# FMC_EEPROM.net
KiCad netlist of a schematic drawn in Altium Designer
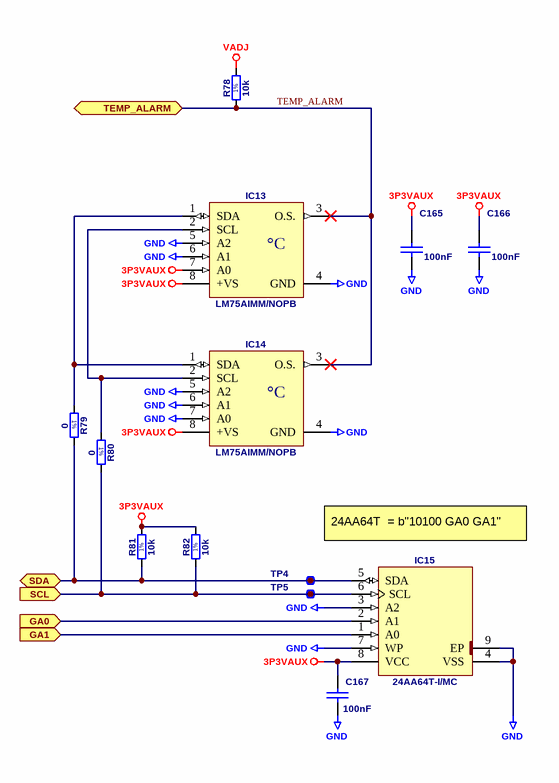
[diagram p0: FMC_EEPROM.SchDoc]

(export (version "E")
  (design (tool "Eeschema 10.0.6"))
  (components
    (comp (ref "C165")
      (value "100nF")
      (footprint "CAPC0603X33N")
      (description "Non-polarised capacitor")
      (fields
        (field (name "PART NUMBER") "CC0201_100NF_6.3V_10%_X5R")
        (field (name "VOLTAGE") "6.3V")
        (field (name "AUTHOR") "CERN DEM JLC")
      )
      (libsource (lib "Capacitors") (part "Capacitor - non polarized"))
    )
    (comp (ref "C166")
      (value "100nF")
      (footprint "CAPC0603X33N")
      (description "Non-polarised capacitor")
      (fields
        (field (name "PART NUMBER") "CC0201_100NF_6.3V_10%_X5R")
        (field (name "VOLTAGE") "6.3V")
        (field (name "AUTHOR") "CERN DEM JLC")
      )
      (libsource (lib "Capacitors") (part "Capacitor - non polarized"))
    )
    (comp (ref "C167")
      (value "100nF")
      (footprint "CAPC0603X33N")
      (description "Non-polarised capacitor")
      (fields
        (field (name "PART NUMBER") "CC0201_100NF_6.3V_10%_X5R")
        (field (name "VOLTAGE") "6.3V")
        (field (name "AUTHOR") "CERN DEM JLC")
      )
      (libsource (lib "Capacitors") (part "Capacitor - non polarized"))
    )
    (comp (ref "IC13")
      (value "LM75AIMM/NOPB")
      (footprint "SOP65P490X109-8N")
      (description "Digital Temperature Sensor and Thermal Watchdog with Two-Wire Interface")
      (fields (field (name "MANUFACTURER") "TEXAS INSTRUMENTS") (field (name "AUTHOR") "CERN DEM JLC"))
      (libsource (lib "ICs And Semiconductors") (part "LM75"))
    )
    (comp (ref "IC14")
      (value "LM75AIMM/NOPB")
      (footprint "SOP65P490X109-8N")
      (description "Digital Temperature Sensor and Thermal Watchdog with Two-Wire Interface")
      (fields (field (name "MANUFACTURER") "TEXAS INSTRUMENTS") (field (name "AUTHOR") "CERN DEM JLC"))
      (libsource (lib "ICs And Semiconductors") (part "LM75"))
    )
    (comp (ref "IC15")
      (value "24AA64T-I/MC")
      (footprint "SON50P300X200X100-9N-S175X155")
      (description "1.7-5.5V 64K I2C Serial EEPROM")
      (fields (field (name "MANUFACTURER") "MICROCHIP TECHNOLOGY") (field (name "AUTHOR") "CERN DEM JLC"))
      (libsource (lib "ICs And Semiconductors") (part "24AA64T-I/MC"))
    )
    (comp (ref "R78")
      (value "10k")
      (footprint "RESC1005X40N")
      (description "Resistor - 1%")
      (fields
        (field (name "PART NUMBER") "R0402_10K_1%_0.0625W_100PPM")
        (field (name "POWER") "0.0625W")
        (field (name "AUTHOR") "CERN DEM JLC")
      )
      (libsource (lib "Resistors") (part "Resistor - 1%"))
    )
    (comp (ref "R79")
      (value "0")
      (footprint "RESC1005X40N")
      (description "Resistor - 1%")
      (fields
        (field (name "PART NUMBER") "R0402_0R_JUMPER")
        (field (name "MANUFACTURER") "GENERIC")
        (field (name "AUTHOR") "CERN DEM JLC")
      )
      (libsource (lib "Resistors") (part "Resistor - 1%"))
    )
    (comp (ref "R80")
      (value "0")
      (footprint "RESC1005X40N")
      (description "Resistor - 1%")
      (fields
        (field (name "PART NUMBER") "R0402_0R_JUMPER")
        (field (name "MANUFACTURER") "GENERIC")
        (field (name "AUTHOR") "CERN DEM JLC")
      )
      (libsource (lib "Resistors") (part "Resistor - 1%"))
    )
    (comp (ref "R81")
      (value "10k")
      (footprint "RESC1005X40N")
      (description "Resistor - 1%")
      (fields
        (field (name "PART NUMBER") "R0402_10K_1%_0.0625W_100PPM")
        (field (name "POWER") "0.0625W")
        (field (name "AUTHOR") "CERN DEM JLC")
      )
      (libsource (lib "Resistors") (part "Resistor - 1%"))
    )
    (comp (ref "R82")
      (value "10k")
      (footprint "RESC1005X40N")
      (description "Resistor - 1%")
      (fields
        (field (name "PART NUMBER") "R0402_10K_1%_0.0625W_100PPM")
        (field (name "POWER") "0.0625W")
        (field (name "AUTHOR") "CERN DEM JLC")
      )
      (libsource (lib "Resistors") (part "Resistor - 1%"))
    )
    (comp (ref "TP4")
      (value "SMD Pad")
      (footprint "C100")
      (description "Through Hole Pad")
      (fields (field (name "PART NUMBER") "SMD_PAD_D1MM") (field (name "AUTHOR") "CERN DEM JLC"))
      (libsource (lib "Eletro-mechanical") (part "Single SMD Pad (Round)"))
    )
    (comp (ref "TP5")
      (value "SMD Pad")
      (footprint "C100")
      (description "Through Hole Pad")
      (fields (field (name "PART NUMBER") "SMD_PAD_D1MM") (field (name "AUTHOR") "CERN DEM JLC"))
      (libsource (lib "Eletro-mechanical") (part "Single SMD Pad (Round)"))
    )
  )
  (nets
    (net (code "1") (name "/GA0") (class "Default")
      (node (ref "IC15") (pin "2") (pinfunction "A1_2") (pintype "input"))
    )
    (net (code "2") (name "/GA1") (class "Default")
      (node (ref "IC15") (pin "1") (pinfunction "A0_1") (pintype "input"))
    )
    (net (code "3") (name "/SCL") (class "Default")
      (node (ref "IC15") (pin "6") (pinfunction "SCL_6") (pintype "input"))
      (node (ref "R80") (pin "2") (pinfunction "2_2") (pintype "passive"))
      (node (ref "R82") (pin "1") (pinfunction "1_1") (pintype "passive"))
      (node (ref "TP5") (pin "1") (pinfunction "1_1") (pintype "bidirectional"))
    )
    (net (code "4") (name "/SDA") (class "Default")
      (node (ref "IC15") (pin "5") (pinfunction "SDA_5") (pintype "bidirectional"))
      (node (ref "R79") (pin "2") (pinfunction "2_2") (pintype "passive"))
      (node (ref "R81") (pin "1") (pinfunction "1_1") (pintype "passive"))
      (node (ref "TP4") (pin "1") (pinfunction "1_1") (pintype "bidirectional"))
    )
    (net (code "5") (name "/TEMP_ALARM") (class "Default")
      (node (ref "IC13") (pin "3") (pinfunction "O.S._3") (pintype "output"))
      (node (ref "IC14") (pin "3") (pinfunction "O.S._3") (pintype "output"))
      (node (ref "R78") (pin "1") (pinfunction "1_1") (pintype "passive"))
    )
    (net (code "6") (name "3P3VAUX") (class "Default")
      (node (ref "C165") (pin "1") (pinfunction "1_1") (pintype "passive"))
      (node (ref "C166") (pin "1") (pinfunction "1_1") (pintype "passive"))
      (node (ref "C167") (pin "1") (pinfunction "1_1") (pintype "passive"))
      (node (ref "IC13") (pin "7") (pinfunction "A0_7") (pintype "input"))
      (node (ref "IC13") (pin "8") (pinfunction "+VS_8") (pintype "power_in"))
      (node (ref "IC14") (pin "8") (pinfunction "+VS_8") (pintype "power_in"))
      (node (ref "IC15") (pin "8") (pinfunction "VCC_8") (pintype "power_in"))
      (node (ref "R81") (pin "2") (pinfunction "2_2") (pintype "passive"))
      (node (ref "R82") (pin "2") (pinfunction "2_2") (pintype "passive"))
    )
    (net (code "7") (name "GND") (class "Default")
      (node (ref "C165") (pin "2") (pinfunction "2_2") (pintype "passive"))
      (node (ref "C166") (pin "2") (pinfunction "2_2") (pintype "passive"))
      (node (ref "C167") (pin "2") (pinfunction "2_2") (pintype "passive"))
      (node (ref "IC13") (pin "4") (pinfunction "GND_4") (pintype "power_in"))
      (node (ref "IC13") (pin "5") (pinfunction "A2_5") (pintype "input"))
      (node (ref "IC13") (pin "6") (pinfunction "A1_6") (pintype "input"))
      (node (ref "IC14") (pin "4") (pinfunction "GND_4") (pintype "power_in"))
      (node (ref "IC14") (pin "5") (pinfunction "A2_5") (pintype "input"))
      (node (ref "IC14") (pin "6") (pinfunction "A1_6") (pintype "input"))
      (node (ref "IC14") (pin "7") (pinfunction "A0_7") (pintype "input"))
      (node (ref "IC15") (pin "3") (pinfunction "A2_3") (pintype "input"))
      (node (ref "IC15") (pin "4") (pinfunction "VSS_4") (pintype "power_in"))
      (node (ref "IC15") (pin "7") (pinfunction "WP_7") (pintype "input"))
      (node (ref "IC15") (pin "9") (pinfunction "EP_9") (pintype "power_in"))
    )
    (net (code "8") (name "Net-(IC13-SCL)") (class "Default")
      (node (ref "IC13") (pin "2") (pinfunction "SCL_2") (pintype "input"))
      (node (ref "IC14") (pin "2") (pinfunction "SCL_2") (pintype "input"))
      (node (ref "R80") (pin "1") (pinfunction "1_1") (pintype "passive"))
    )
    (net (code "9") (name "Net-(IC13-SDA)") (class "Default")
      (node (ref "IC13") (pin "1") (pinfunction "SDA_1") (pintype "bidirectional"))
      (node (ref "IC14") (pin "1") (pinfunction "SDA_1") (pintype "bidirectional"))
      (node (ref "R79") (pin "1") (pinfunction "1_1") (pintype "passive"))
    )
    (net (code "10") (name "VADJ") (class "Default")
      (node (ref "R78") (pin "2") (pinfunction "2_2") (pintype "passive"))
    )
  )
)
